# MiniRobot.net
KiCad netlist of a schematic drawn in EAGLE
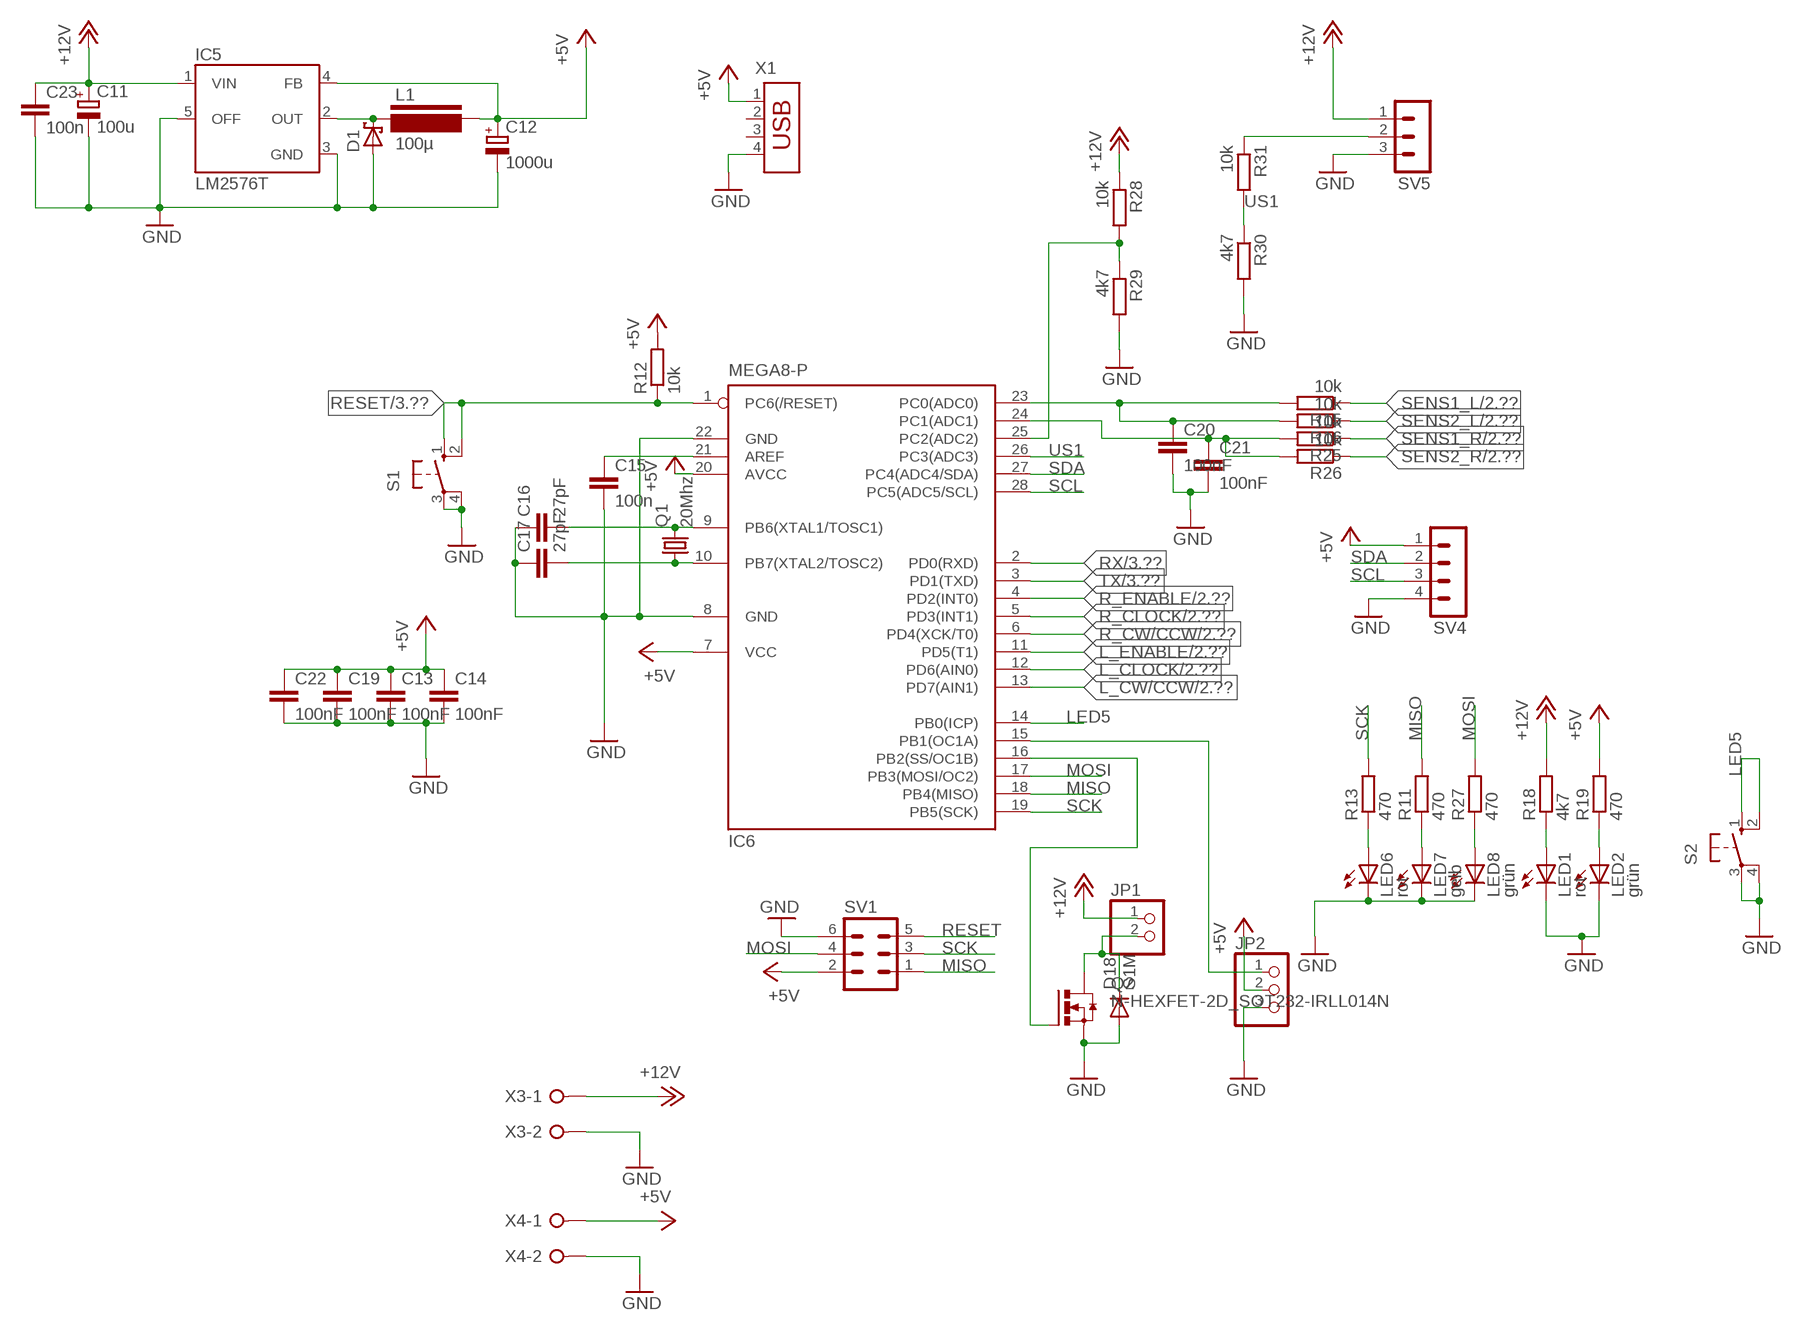
[diagram p0: schematic, sheet 1]
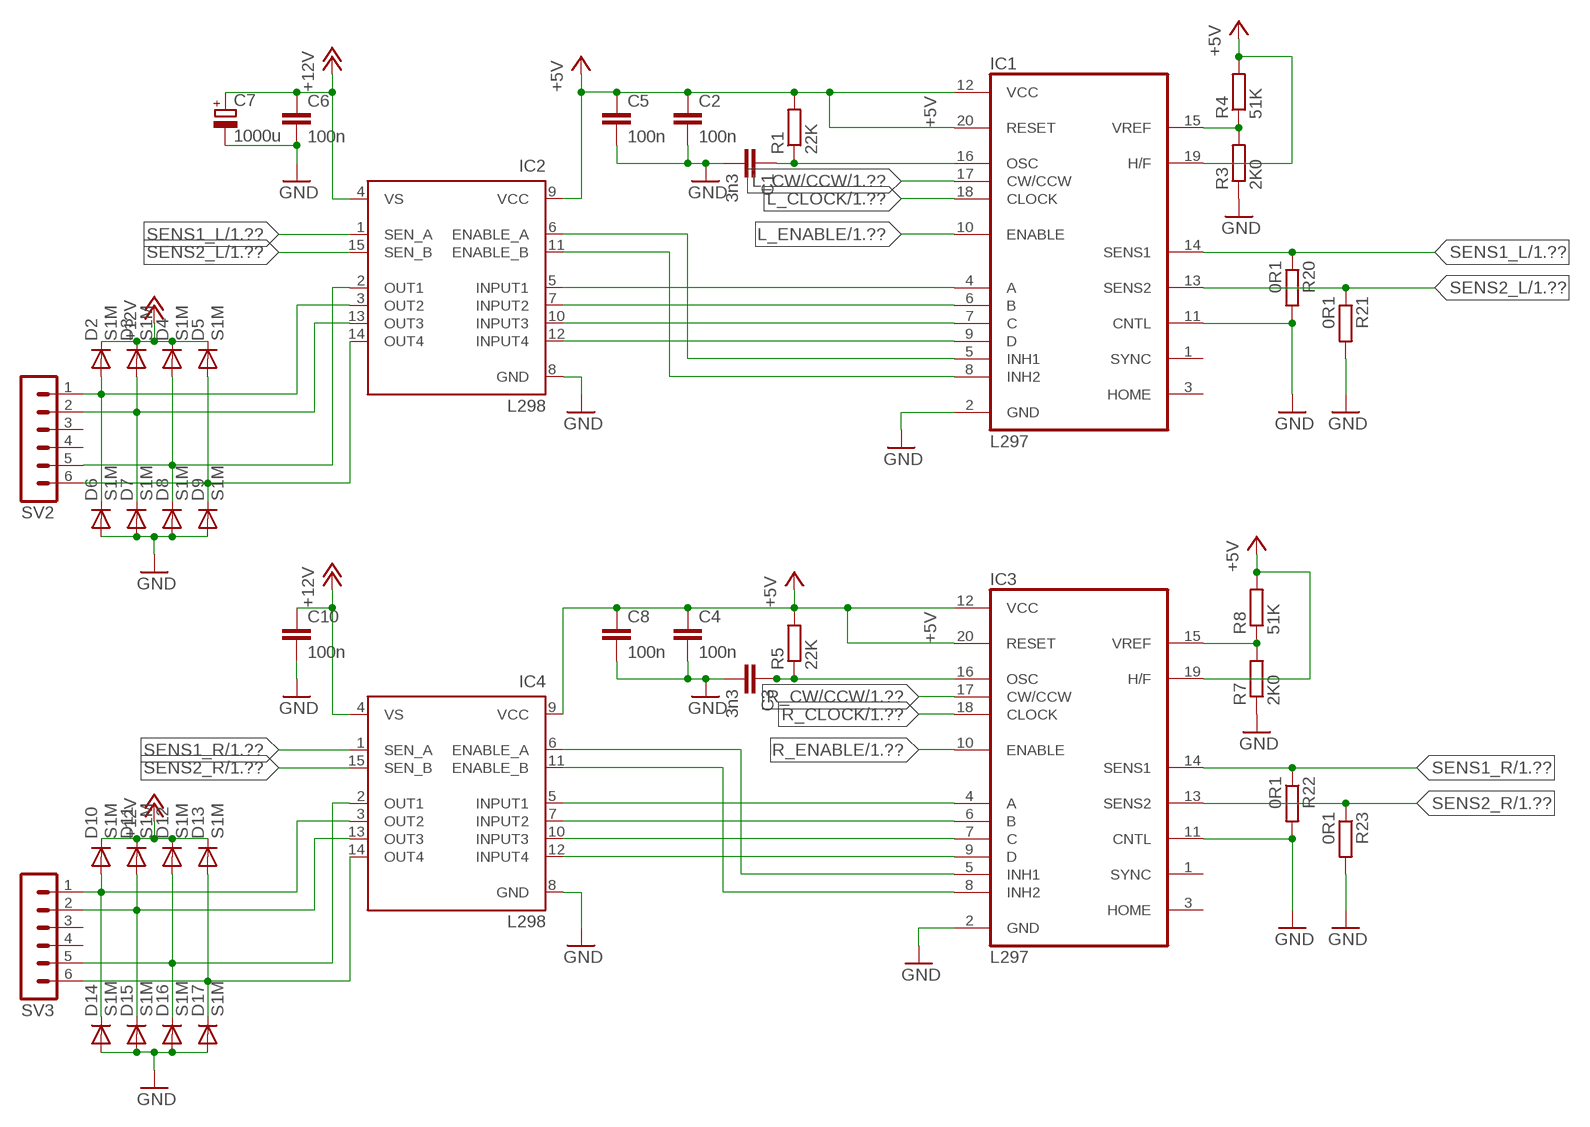
[diagram p1: schematic, sheet 2]
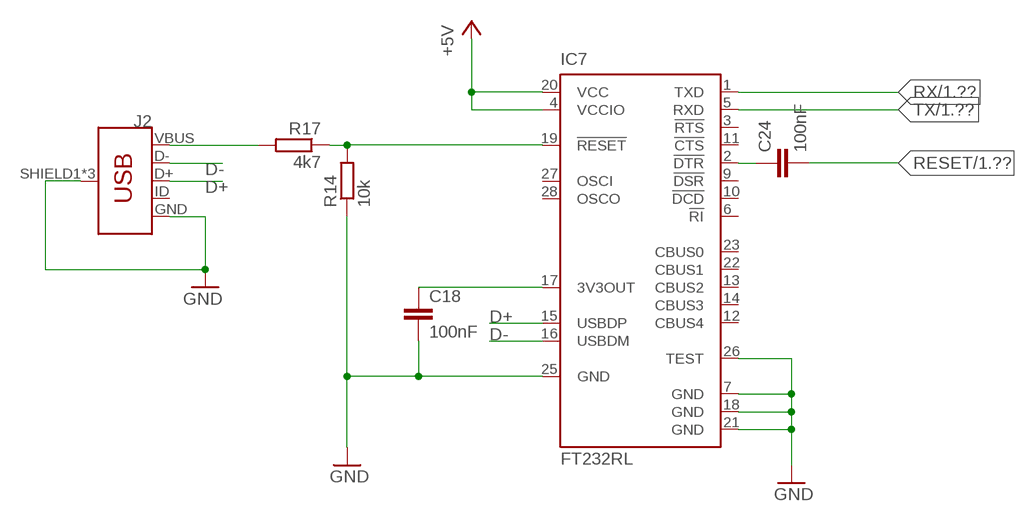
[diagram p2: schematic, sheet 3]

(export (version "E")
  (design (tool "Eeschema 10.0.6"))
  (components
    (comp (ref "C11")
      (value "100u")
      (footprint "eagle-import:E5-10,5")
      (libsource (lib "eagle-import") (part "CPOL-EUE5-10.5"))
    )
    (comp (ref "C12")
      (value "1000u")
      (footprint "eagle-import:E5-10,5")
      (libsource (lib "eagle-import") (part "CPOL-EUE5-10.5"))
    )
    (comp (ref "C13")
      (value "100nF")
      (footprint "eagle-import:C0805")
      (libsource (lib "eagle-import") (part "C-EUC0805"))
    )
    (comp (ref "C14")
      (value "100nF")
      (footprint "eagle-import:C0805")
      (libsource (lib "eagle-import") (part "C-EUC0805"))
    )
    (comp (ref "C15")
      (value "100n")
      (footprint "eagle-import:C0805")
      (libsource (lib "eagle-import") (part "C-EUC0805"))
    )
    (comp (ref "C16")
      (value "27pF")
      (footprint "eagle-import:C0805")
      (libsource (lib "eagle-import") (part "C-EUC0805"))
    )
    (comp (ref "C17")
      (value "27pF")
      (footprint "eagle-import:C0805")
      (libsource (lib "eagle-import") (part "C-EUC0805"))
    )
    (comp (ref "C19")
      (value "100nF")
      (footprint "eagle-import:C0805")
      (libsource (lib "eagle-import") (part "C-EUC0805"))
    )
    (comp (ref "C20")
      (value "100nF")
      (footprint "eagle-import:C0805")
      (libsource (lib "eagle-import") (part "C-EUC0805"))
    )
    (comp (ref "C21")
      (value "100nF")
      (footprint "eagle-import:C0805")
      (libsource (lib "eagle-import") (part "C-EUC0805"))
    )
    (comp (ref "C22")
      (value "100nF")
      (footprint "eagle-import:C0805")
      (libsource (lib "eagle-import") (part "C-EUC0805"))
    )
    (comp (ref "C23")
      (value "100n")
      (footprint "eagle-import:C0805")
      (libsource (lib "eagle-import") (part "resistor_C-EUC0805"))
    )
    (comp (ref "D1")
      (value "SCHOTTKY-DIODEF126Z12")
      (footprint "eagle-import:F126Z12")
      (libsource (lib "eagle-import") (part "SCHOTTKY-DIODEF126Z12"))
    )
    (comp (ref "D18")
      (value "S1M")
      (footprint "eagle-import:SMA")
      (libsource (lib "eagle-import") (part "S1M"))
    )
    (comp (ref "IC5")
      (value "LM2576T")
      (footprint "eagle-import:TO220-5")
      (libsource (lib "eagle-import") (part "LM2576T"))
    )
    (comp (ref "IC6")
      (value "MEGA8-P")
      (footprint "eagle-import:DIL28-3")
      (libsource (lib "eagle-import") (part "MEGA8-P"))
    )
    (comp (ref "JP1")
      (value "PINHD-1X2")
      (footprint "eagle-import:1X02")
      (libsource (lib "eagle-import") (part "PINHD-1X2"))
    )
    (comp (ref "JP2")
      (value "PINHD-1X3")
      (footprint "eagle-import:1X03")
      (libsource (lib "eagle-import") (part "PINHD-1X3"))
    )
    (comp (ref "L1")
      (value "100µ")
      (footprint "eagle-import:PISR")
      (libsource (lib "eagle-import") (part "L-PISR"))
    )
    (comp (ref "LED1")
      (value "rot")
      (footprint "eagle-import:CHIP-LED0805")
      (libsource (lib "eagle-import") (part "LEDCHIP-LED0805"))
    )
    (comp (ref "LED2")
      (value "grün")
      (footprint "eagle-import:CHIP-LED0805")
      (libsource (lib "eagle-import") (part "LEDCHIP-LED0805"))
    )
    (comp (ref "LED6")
      (value "rot")
      (footprint "eagle-import:CHIP-LED0805")
      (libsource (lib "eagle-import") (part "LEDCHIP-LED0805"))
    )
    (comp (ref "LED7")
      (value "gelb")
      (footprint "eagle-import:CHIP-LED0805")
      (libsource (lib "eagle-import") (part "LEDCHIP-LED0805"))
    )
    (comp (ref "LED8")
      (value "grün")
      (footprint "eagle-import:CHIP-LED0805")
      (libsource (lib "eagle-import") (part "LEDCHIP-LED0805"))
    )
    (comp (ref "Q1")
      (value "20Mhz")
      (footprint "eagle-import:CSM-7X-DU")
      (libsource (lib "eagle-import") (part "CSM-7X-DU"))
    )
    (comp (ref "Q2")
      (value "N-HEXFET-2D_SOT232-IRLL014N")
      (footprint "eagle-import:SOT223")
      (libsource (lib "eagle-import") (part "N-HEXFET-2D_?-SOT232IRLL014N"))
    )
    (comp (ref "R11")
      (value "470")
      (footprint "eagle-import:M0805")
      (libsource (lib "eagle-import") (part "R-EU_M0805"))
    )
    (comp (ref "R12")
      (value "10k")
      (footprint "eagle-import:R0805")
      (libsource (lib "eagle-import") (part "R-EU_R0805"))
    )
    (comp (ref "R13")
      (value "470")
      (footprint "eagle-import:M0805")
      (libsource (lib "eagle-import") (part "R-EU_M0805"))
    )
    (comp (ref "R15")
      (value "10k")
      (footprint "eagle-import:R0805")
      (libsource (lib "eagle-import") (part "R-EU_R0805"))
    )
    (comp (ref "R16")
      (value "10k")
      (footprint "eagle-import:M0805")
      (libsource (lib "eagle-import") (part "R-EU_M0805"))
    )
    (comp (ref "R18")
      (value "4k7")
      (footprint "eagle-import:R0805")
      (libsource (lib "eagle-import") (part "R-EU_R0805"))
    )
    (comp (ref "R19")
      (value "470")
      (footprint "eagle-import:M0805")
      (libsource (lib "eagle-import") (part "R-EU_M0805"))
    )
    (comp (ref "R25")
      (value "10k")
      (footprint "eagle-import:M0805")
      (libsource (lib "eagle-import") (part "R-EU_M0805"))
    )
    (comp (ref "R26")
      (value "10k")
      (footprint "eagle-import:M0805")
      (libsource (lib "eagle-import") (part "R-EU_M0805"))
    )
    (comp (ref "R27")
      (value "470")
      (footprint "eagle-import:R0805")
      (libsource (lib "eagle-import") (part "R-EU_R0805"))
    )
    (comp (ref "R28")
      (value "10k")
      (footprint "eagle-import:M0805")
      (libsource (lib "eagle-import") (part "R-EU_M0805"))
    )
    (comp (ref "R29")
      (value "4k7")
      (footprint "eagle-import:M0805")
      (libsource (lib "eagle-import") (part "R-EU_M0805"))
    )
    (comp (ref "R30")
      (value "4k7")
      (footprint "eagle-import:R0805")
      (libsource (lib "eagle-import") (part "R-EU_R0805"))
    )
    (comp (ref "R31")
      (value "10k")
      (footprint "eagle-import:R0805")
      (libsource (lib "eagle-import") (part "R-EU_R0805"))
    )
    (comp (ref "S1")
      (value "10-XX")
      (footprint "eagle-import:B3F-10XX")
      (fields (field (name "MPN") "B3F-1000"))
      (libsource (lib "eagle-import") (part "10-XX"))
    )
    (comp (ref "S2")
      (value "10-XX")
      (footprint "eagle-import:B3F-10XX")
      (fields (field (name "MPN") "B3F-1000"))
      (libsource (lib "eagle-import") (part "10-XX"))
    )
    (comp (ref "SV1")
      (value "ML6")
      (footprint "eagle-import:ML6")
      (libsource (lib "eagle-import") (part "ML6"))
    )
    (comp (ref "SV4")
      (value "MA04-1")
      (footprint "eagle-import:MA04-1")
      (libsource (lib "eagle-import") (part "MA04-1"))
    )
    (comp (ref "SV5")
      (value "MA03-1")
      (footprint "eagle-import:MA03-1")
      (libsource (lib "eagle-import") (part "MA03-1"))
    )
    (comp (ref "X1")
      (value "USB-787616")
      (footprint "eagle-import:USB")
      (libsource (lib "eagle-import") (part "USB-787616"))
    )
    (comp (ref "X3")
      (value "W237-02P")
      (footprint "eagle-import:W237-132")
      (libsource (lib "eagle-import") (part "W237-02P"))
    )
    (comp (ref "X4")
      (value "W237-02P")
      (footprint "eagle-import:W237-132")
      (libsource (lib "eagle-import") (part "W237-02P"))
    )
    (comp (ref "C1")
      (value "3n3")
      (footprint "eagle-import:C0805")
      (libsource (lib "eagle-import") (part "resistor_C-EUC0805"))
    )
    (comp (ref "C2")
      (value "100n")
      (footprint "eagle-import:C0805")
      (libsource (lib "eagle-import") (part "resistor_C-EUC0805"))
    )
    (comp (ref "C3")
      (value "3n3")
      (footprint "eagle-import:C0805")
      (libsource (lib "eagle-import") (part "resistor_C-EUC0805"))
    )
    (comp (ref "C4")
      (value "100n")
      (footprint "eagle-import:C0805")
      (libsource (lib "eagle-import") (part "resistor_C-EUC0805"))
    )
    (comp (ref "C5")
      (value "100n")
      (footprint "eagle-import:C0805")
      (libsource (lib "eagle-import") (part "resistor_C-EUC0805"))
    )
    (comp (ref "C6")
      (value "100n")
      (footprint "eagle-import:C0805")
      (libsource (lib "eagle-import") (part "resistor_C-EUC0805"))
    )
    (comp (ref "C7")
      (value "1000u")
      (footprint "eagle-import:E5-10,5")
      (libsource (lib "eagle-import") (part "CPOL-EUE5-10.5"))
    )
    (comp (ref "C8")
      (value "100n")
      (footprint "eagle-import:C0805")
      (libsource (lib "eagle-import") (part "resistor_C-EUC0805"))
    )
    (comp (ref "C10")
      (value "100n")
      (footprint "eagle-import:C0805")
      (libsource (lib "eagle-import") (part "resistor_C-EUC0805"))
    )
    (comp (ref "D2")
      (value "S1M")
      (footprint "eagle-import:SMA")
      (libsource (lib "eagle-import") (part "S1M"))
    )
    (comp (ref "D3")
      (value "S1M")
      (footprint "eagle-import:SMA")
      (libsource (lib "eagle-import") (part "S1M"))
    )
    (comp (ref "D4")
      (value "S1M")
      (footprint "eagle-import:SMA")
      (libsource (lib "eagle-import") (part "S1M"))
    )
    (comp (ref "D5")
      (value "S1M")
      (footprint "eagle-import:SMA")
      (libsource (lib "eagle-import") (part "S1M"))
    )
    (comp (ref "D6")
      (value "S1M")
      (footprint "eagle-import:SMA")
      (libsource (lib "eagle-import") (part "S1M"))
    )
    (comp (ref "D7")
      (value "S1M")
      (footprint "eagle-import:SMA")
      (libsource (lib "eagle-import") (part "S1M"))
    )
    (comp (ref "D8")
      (value "S1M")
      (footprint "eagle-import:SMA")
      (libsource (lib "eagle-import") (part "S1M"))
    )
    (comp (ref "D9")
      (value "S1M")
      (footprint "eagle-import:SMA")
      (libsource (lib "eagle-import") (part "S1M"))
    )
    (comp (ref "D10")
      (value "S1M")
      (footprint "eagle-import:SMA")
      (libsource (lib "eagle-import") (part "S1M"))
    )
    (comp (ref "D11")
      (value "S1M")
      (footprint "eagle-import:SMA")
      (libsource (lib "eagle-import") (part "S1M"))
    )
    (comp (ref "D12")
      (value "S1M")
      (footprint "eagle-import:SMA")
      (libsource (lib "eagle-import") (part "S1M"))
    )
    (comp (ref "D13")
      (value "S1M")
      (footprint "eagle-import:SMA")
      (libsource (lib "eagle-import") (part "S1M"))
    )
    (comp (ref "D14")
      (value "S1M")
      (footprint "eagle-import:SMA")
      (libsource (lib "eagle-import") (part "S1M"))
    )
    (comp (ref "D15")
      (value "S1M")
      (footprint "eagle-import:SMA")
      (libsource (lib "eagle-import") (part "S1M"))
    )
    (comp (ref "D16")
      (value "S1M")
      (footprint "eagle-import:SMA")
      (libsource (lib "eagle-import") (part "S1M"))
    )
    (comp (ref "D17")
      (value "S1M")
      (footprint "eagle-import:SMA")
      (libsource (lib "eagle-import") (part "S1M"))
    )
    (comp (ref "IC1")
      (value "L297")
      (footprint "eagle-import:DIL20")
      (fields (field (name "MPN") "L297/1"))
      (libsource (lib "eagle-import") (part "L297"))
    )
    (comp (ref "IC2")
      (value "L298")
      (footprint "eagle-import:MULTIWATT-15")
      (fields (field (name "MPN") "L298N"))
      (libsource (lib "eagle-import") (part "L298"))
    )
    (comp (ref "IC3")
      (value "L297")
      (footprint "eagle-import:DIL20")
      (fields (field (name "MPN") "L297/1"))
      (libsource (lib "eagle-import") (part "L297"))
    )
    (comp (ref "IC4")
      (value "L298")
      (footprint "eagle-import:MULTIWATT-15")
      (fields (field (name "MPN") "L298N"))
      (libsource (lib "eagle-import") (part "L298"))
    )
    (comp (ref "R1")
      (value "22K")
      (footprint "eagle-import:R0805")
      (libsource (lib "eagle-import") (part "R-EU_R0805"))
    )
    (comp (ref "R3")
      (value "2K0")
      (footprint "eagle-import:R0805")
      (libsource (lib "eagle-import") (part "R-EU_R0805"))
    )
    (comp (ref "R4")
      (value "51K")
      (footprint "eagle-import:R0805")
      (libsource (lib "eagle-import") (part "R-EU_R0805"))
    )
    (comp (ref "R5")
      (value "22K")
      (footprint "eagle-import:R0805")
      (libsource (lib "eagle-import") (part "R-EU_R0805"))
    )
    (comp (ref "R7")
      (value "2K0")
      (footprint "eagle-import:R0805")
      (libsource (lib "eagle-import") (part "R-EU_R0805"))
    )
    (comp (ref "R8")
      (value "51K")
      (footprint "eagle-import:R0805")
      (libsource (lib "eagle-import") (part "R-EU_R0805"))
    )
    (comp (ref "R20")
      (value "0R1")
      (footprint "eagle-import:P0613_15")
      (libsource (lib "eagle-import") (part "R-EU_0613/15"))
    )
    (comp (ref "R21")
      (value "0R1")
      (footprint "eagle-import:P0613_15")
      (libsource (lib "eagle-import") (part "R-EU_0613/15"))
    )
    (comp (ref "R22")
      (value "0R1")
      (footprint "eagle-import:P0613_15")
      (libsource (lib "eagle-import") (part "R-EU_0613/15"))
    )
    (comp (ref "R23")
      (value "0R1")
      (footprint "eagle-import:P0613_15")
      (libsource (lib "eagle-import") (part "R-EU_0613/15"))
    )
    (comp (ref "SV2")
      (value "MA06-1")
      (footprint "eagle-import:MA06-1")
      (libsource (lib "eagle-import") (part "MA06-1"))
    )
    (comp (ref "SV3")
      (value "MA06-1")
      (footprint "eagle-import:MA06-1")
      (libsource (lib "eagle-import") (part "MA06-1"))
    )
    (comp (ref "C18")
      (value "100nF")
      (footprint "eagle-import:C0805")
      (libsource (lib "eagle-import") (part "C-EUC0805"))
    )
    (comp (ref "C24")
      (value "100nF")
      (footprint "eagle-import:C0805")
      (libsource (lib "eagle-import") (part "C-EUC0805"))
    )
    (comp (ref "IC7")
      (value "FT232RL")
      (footprint "eagle-import:SSOP28")
      (libsource (lib "eagle-import") (part "FT232RL"))
    )
    (comp (ref "J2")
      (value "USB_MICRO-B_FEMALE-SMT")
      (footprint "eagle-import:USB-B-MICRO-SMD")
      (libsource (lib "eagle-import") (part "USB_MICRO-B_FEMALE-SMT"))
    )
    (comp (ref "R14")
      (value "10k")
      (footprint "eagle-import:M0805")
      (libsource (lib "eagle-import") (part "R-EU_M0805"))
    )
    (comp (ref "R17")
      (value "4k7")
      (footprint "eagle-import:M0805")
      (libsource (lib "eagle-import") (part "R-EU_M0805"))
    )
  )
  (nets
    (net (code "1") (name "+5V") (class "Default")
      (node (ref "C12") (pin "+") (pinfunction "+_+") (pintype "passive"))
      (node (ref "C13") (pin "1") (pinfunction "1_1") (pintype "passive"))
      (node (ref "C14") (pin "1") (pinfunction "1_1") (pintype "passive"))
      (node (ref "C19") (pin "1") (pinfunction "1_1") (pintype "passive"))
      (node (ref "C2") (pin "1") (pinfunction "1_1") (pintype "passive"))
      (node (ref "C22") (pin "1") (pinfunction "1_1") (pintype "passive"))
      (node (ref "C4") (pin "1") (pinfunction "1_1") (pintype "passive"))
      (node (ref "C5") (pin "1") (pinfunction "1_1") (pintype "passive"))
      (node (ref "C8") (pin "1") (pinfunction "1_1") (pintype "passive"))
      (node (ref "IC1") (pin "12") (pinfunction "VCC_12") (pintype "power_in"))
      (node (ref "IC1") (pin "19") (pinfunction "H/F_19") (pintype "input"))
      (node (ref "IC1") (pin "20") (pinfunction "RESET_20") (pintype "input"))
      (node (ref "IC2") (pin "9") (pinfunction "VCC_9") (pintype "power_in"))
      (node (ref "IC3") (pin "12") (pinfunction "VCC_12") (pintype "power_in"))
      (node (ref "IC3") (pin "19") (pinfunction "H/F_19") (pintype "input"))
      (node (ref "IC3") (pin "20") (pinfunction "RESET_20") (pintype "input"))
      (node (ref "IC4") (pin "9") (pinfunction "VCC_9") (pintype "power_in"))
      (node (ref "IC5") (pin "4") (pinfunction "FB_4") (pintype "input"))
      (node (ref "IC6") (pin "20") (pinfunction "AVCC_20") (pintype "power_in"))
      (node (ref "IC6") (pin "7") (pinfunction "VCC_7") (pintype "power_in"))
      (node (ref "IC7") (pin "20") (pinfunction "VCC_20") (pintype "power_in"))
      (node (ref "IC7") (pin "4") (pinfunction "VCCIO_4") (pintype "power_in"))
      (node (ref "JP2") (pin "2") (pinfunction "2_2") (pintype "passive"))
      (node (ref "L1") (pin "P$2") (pinfunction "P$2_P$2") (pintype "passive"))
      (node (ref "R1") (pin "2") (pinfunction "2_2") (pintype "passive"))
      (node (ref "R12") (pin "2") (pinfunction "2_2") (pintype "passive"))
      (node (ref "R19") (pin "2") (pinfunction "2_2") (pintype "passive"))
      (node (ref "R4") (pin "2") (pinfunction "2_2") (pintype "passive"))
      (node (ref "R5") (pin "2") (pinfunction "2_2") (pintype "passive"))
      (node (ref "R8") (pin "2") (pinfunction "2_2") (pintype "passive"))
      (node (ref "SV1") (pin "2") (pinfunction "2_2") (pintype "passive"))
      (node (ref "SV4") (pin "1") (pinfunction "1_1") (pintype "passive"))
      (node (ref "X1") (pin "1") (pinfunction "1_1") (pintype "passive"))
      (node (ref "X4") (pin "1") (pinfunction "KL_1") (pintype "passive"))
    )
    (net (code "2") (name "+12V") (class "Default")
      (node (ref "C10") (pin "1") (pinfunction "1_1") (pintype "passive"))
      (node (ref "C11") (pin "+") (pinfunction "+_+") (pintype "passive"))
      (node (ref "C23") (pin "1") (pinfunction "1_1") (pintype "passive"))
      (node (ref "C6") (pin "1") (pinfunction "1_1") (pintype "passive"))
      (node (ref "C7") (pin "+") (pinfunction "+_+") (pintype "passive"))
      (node (ref "D10") (pin "C") (pinfunction "C_C") (pintype "passive"))
      (node (ref "D11") (pin "C") (pinfunction "C_C") (pintype "passive"))
      (node (ref "D12") (pin "C") (pinfunction "C_C") (pintype "passive"))
      (node (ref "D13") (pin "C") (pinfunction "C_C") (pintype "passive"))
      (node (ref "D2") (pin "C") (pinfunction "C_C") (pintype "passive"))
      (node (ref "D3") (pin "C") (pinfunction "C_C") (pintype "passive"))
      (node (ref "D4") (pin "C") (pinfunction "C_C") (pintype "passive"))
      (node (ref "D5") (pin "C") (pinfunction "C_C") (pintype "passive"))
      (node (ref "IC2") (pin "4") (pinfunction "VS_4") (pintype "power_in"))
      (node (ref "IC4") (pin "4") (pinfunction "VS_4") (pintype "power_in"))
      (node (ref "IC5") (pin "1") (pinfunction "VIN_1") (pintype "power_in"))
      (node (ref "JP1") (pin "1") (pinfunction "1_1") (pintype "passive"))
      (node (ref "R18") (pin "2") (pinfunction "2_2") (pintype "passive"))
      (node (ref "R28") (pin "1") (pinfunction "1_1") (pintype "passive"))
      (node (ref "SV5") (pin "1") (pinfunction "1_1") (pintype "passive"))
      (node (ref "X3") (pin "1") (pinfunction "KL_1") (pintype "passive"))
    )
    (net (code "3") (name "D+") (class "Default")
      (node (ref "IC7") (pin "15") (pinfunction "USBDP_15") (pintype "bidirectional"))
      (node (ref "J2") (pin "D+") (pinfunction "D+_D+") (pintype "bidirectional"))
    )
    (net (code "4") (name "D-") (class "Default")
      (node (ref "IC7") (pin "16") (pinfunction "USBDM_16") (pintype "bidirectional"))
      (node (ref "J2") (pin "D-") (pinfunction "D-_D-") (pintype "bidirectional"))
    )
    (net (code "5") (name "GND") (class "Default")
      (node (ref "C1") (pin "2") (pinfunction "2_2") (pintype "passive"))
      (node (ref "C10") (pin "2") (pinfunction "2_2") (pintype "passive"))
      (node (ref "C11") (pin "-") (pinfunction "-_-") (pintype "passive"))
      (node (ref "C12") (pin "-") (pinfunction "-_-") (pintype "passive"))
      (node (ref "C13") (pin "2") (pinfunction "2_2") (pintype "passive"))
      (node (ref "C14") (pin "2") (pinfunction "2_2") (pintype "passive"))
      (node (ref "C15") (pin "2") (pinfunction "2_2") (pintype "passive"))
      (node (ref "C16") (pin "1") (pinfunction "1_1") (pintype "passive"))
      (node (ref "C17") (pin "1") (pinfunction "1_1") (pintype "passive"))
      (node (ref "C18") (pin "2") (pinfunction "2_2") (pintype "passive"))
      (node (ref "C19") (pin "2") (pinfunction "2_2") (pintype "passive"))
      (node (ref "C2") (pin "2") (pinfunction "2_2") (pintype "passive"))
      (node (ref "C20") (pin "2") (pinfunction "2_2") (pintype "passive"))
      (node (ref "C21") (pin "2") (pinfunction "2_2") (pintype "passive"))
      (node (ref "C22") (pin "2") (pinfunction "2_2") (pintype "passive"))
      (node (ref "C23") (pin "2") (pinfunction "2_2") (pintype "passive"))
      (node (ref "C3") (pin "2") (pinfunction "2_2") (pintype "passive"))
      (node (ref "C4") (pin "2") (pinfunction "2_2") (pintype "passive"))
      (node (ref "C5") (pin "2") (pinfunction "2_2") (pintype "passive"))
      (node (ref "C6") (pin "2") (pinfunction "2_2") (pintype "passive"))
      (node (ref "C7") (pin "-") (pinfunction "-_-") (pintype "passive"))
      (node (ref "C8") (pin "2") (pinfunction "2_2") (pintype "passive"))
      (node (ref "D1") (pin "A") (pinfunction "A_A") (pintype "passive"))
      (node (ref "D14") (pin "A") (pinfunction "A_A") (pintype "passive"))
      (node (ref "D15") (pin "A") (pinfunction "A_A") (pintype "passive"))
      (node (ref "D16") (pin "A") (pinfunction "A_A") (pintype "passive"))
      (node (ref "D17") (pin "A") (pinfunction "A_A") (pintype "passive"))
      (node (ref "D18") (pin "A") (pinfunction "A_A") (pintype "passive"))
      (node (ref "D6") (pin "A") (pinfunction "A_A") (pintype "passive"))
      (node (ref "D7") (pin "A") (pinfunction "A_A") (pintype "passive"))
      (node (ref "D8") (pin "A") (pinfunction "A_A") (pintype "passive"))
      (node (ref "D9") (pin "A") (pinfunction "A_A") (pintype "passive"))
      (node (ref "IC1") (pin "11") (pinfunction "CNTL_11") (pintype "input"))
      (node (ref "IC1") (pin "2") (pinfunction "GND_2") (pintype "power_in"))
      (node (ref "IC2") (pin "8") (pinfunction "GND_8") (pintype "power_in"))
      (node (ref "IC3") (pin "11") (pinfunction "CNTL_11") (pintype "input"))
      (node (ref "IC3") (pin "2") (pinfunction "GND_2") (pintype "power_in"))
      (node (ref "IC4") (pin "8") (pinfunction "GND_8") (pintype "power_in"))
      (node (ref "IC5") (pin "3") (pinfunction "GND_3") (pintype "power_in"))
      (node (ref "IC5") (pin "5") (pinfunction "OFF_5") (pintype "input"))
      (node (ref "IC6") (pin "22") (pinfunction "GND_22") (pintype "power_in"))
      (node (ref "IC6") (pin "8") (pinfunction "GND_8") (pintype "power_in"))
      (node (ref "IC7") (pin "18") (pinfunction "GND_18") (pintype "power_in"))
      (node (ref "IC7") (pin "21") (pinfunction "GND_21") (pintype "power_in"))
      (node (ref "IC7") (pin "25") (pinfunction "GND_25") (pintype "power_in"))
      (node (ref "IC7") (pin "26") (pinfunction "TEST_26") (pintype "input"))
      (node (ref "IC7") (pin "7") (pinfunction "GND_7") (pintype "power_in"))
      (node (ref "J2") (pin "GND") (pinfunction "GND_GND") (pintype "power_in"))
      (node (ref "J2") (pin "SHIELD1") (pinfunction "SHIELD_SHIELD1") (pintype "bidirectional"))
      (node (ref "J2") (pin "SHIELD2") (pinfunction "SHIELD_SHIELD2") (pintype "bidirectional"))
      (node (ref "J2") (pin "SHIELD3") (pinfunction "SHIELD_SHIELD3") (pintype "bidirectional"))
      (node (ref "JP2") (pin "3") (pinfunction "3_3") (pintype "passive"))
      (node (ref "LED1") (pin "C") (pinfunction "C_C") (pintype "passive"))
      (node (ref "LED2") (pin "C") (pinfunction "C_C") (pintype "passive"))
      (node (ref "LED6") (pin "C") (pinfunction "C_C") (pintype "passive"))
      (node (ref "LED7") (pin "C") (pinfunction "C_C") (pintype "passive"))
      (node (ref "LED8") (pin "C") (pinfunction "C_C") (pintype "passive"))
      (node (ref "Q2") (pin "3") (pinfunction "S_3") (pintype "passive"))
      (node (ref "R14") (pin "1") (pinfunction "1_1") (pintype "passive"))
      (node (ref "R20") (pin "2") (pinfunction "2_2") (pintype "passive"))
      (node (ref "R21") (pin "2") (pinfunction "2_2") (pintype "passive"))
      (node (ref "R22") (pin "2") (pinfunction "2_2") (pintype "passive"))
      (node (ref "R23") (pin "2") (pinfunction "2_2") (pintype "passive"))
      (node (ref "R29") (pin "2") (pinfunction "2_2") (pintype "passive"))
      (node (ref "R3") (pin "1") (pinfunction "1_1") (pintype "passive"))
      (node (ref "R30") (pin "2") (pinfunction "2_2") (pintype "passive"))
      (node (ref "R7") (pin "1") (pinfunction "1_1") (pintype "passive"))
      (node (ref "S1") (pin "3") (pinfunction "P_3") (pintype "passive"))
      (node (ref "S1") (pin "4") (pinfunction "P1_4") (pintype "passive"))
      (node (ref "S2") (pin "3") (pinfunction "P_3") (pintype "passive"))
      (node (ref "S2") (pin "4") (pinfunction "P1_4") (pintype "passive"))
      (node (ref "SV1") (pin "6") (pinfunction "6_6") (pintype "passive"))
      (node (ref "SV4") (pin "4") (pinfunction "4_4") (pintype "passive"))
      (node (ref "SV5") (pin "3") (pinfunction "3_3") (pintype "passive"))
      (node (ref "X1") (pin "4") (pinfunction "4_4") (pintype "passive"))
      (node (ref "X3") (pin "2") (pinfunction "KL_2") (pintype "passive"))
      (node (ref "X4") (pin "2") (pinfunction "KL_2") (pintype "passive"))
    )
    (net (code "6") (name "LED5") (class "Default")
      (node (ref "IC6") (pin "14") (pinfunction "PB0(ICP)_14") (pintype "bidirectional"))
      (node (ref "S2") (pin "1") (pinfunction "S_1") (pintype "passive"))
      (node (ref "S2") (pin "2") (pinfunction "S1_2") (pintype "passive"))
    )
    (net (code "7") (name "L_CLOCK") (class "Default")
      (node (ref "IC1") (pin "18") (pinfunction "CLOCK_18") (pintype "input"))
      (node (ref "IC6") (pin "12") (pinfunction "PD6(AIN0)_12") (pintype "bidirectional"))
    )
    (net (code "8") (name "L_CW{slash}CCW") (class "Default")
      (node (ref "IC1") (pin "17") (pinfunction "CW/CCW_17") (pintype "input"))
      (node (ref "IC6") (pin "13") (pinfunction "PD7(AIN1)_13") (pintype "bidirectional"))
    )
    (net (code "9") (name "L_ENABLE") (class "Default")
      (node (ref "IC1") (pin "10") (pinfunction "ENABLE_10") (pintype "input"))
      (node (ref "IC6") (pin "11") (pinfunction "PD5(T1)_11") (pintype "bidirectional"))
    )
    (net (code "10") (name "MISO") (class "Default")
      (node (ref "IC6") (pin "18") (pinfunction "PB4(MISO)_18") (pintype "bidirectional"))
      (node (ref "R11") (pin "2") (pinfunction "2_2") (pintype "passive"))
      (node (ref "SV1") (pin "1") (pinfunction "1_1") (pintype "passive"))
    )
    (net (code "11") (name "MOSI") (class "Default")
      (node (ref "IC6") (pin "17") (pinfunction "PB3(MOSI/OC2)_17") (pintype "bidirectional"))
      (node (ref "R27") (pin "2") (pinfunction "2_2") (pintype "passive"))
      (node (ref "SV1") (pin "4") (pinfunction "4_4") (pintype "passive"))
    )
    (net (code "12") (name "Net-(D18-PadC)") (class "Default")
      (node (ref "D18") (pin "C") (pinfunction "C_C") (pintype "passive"))
      (node (ref "JP1") (pin "2") (pinfunction "2_2") (pintype "passive"))
      (node (ref "Q2") (pin "2") (pinfunction "D_2") (pintype "passive"))
      (node (ref "Q2") (pin "4") (pinfunction "D_4") (pintype "passive"))
    )
    (net (code "13") (name "Net-(IC1-A)") (class "Default")
      (node (ref "IC1") (pin "4") (pinfunction "A_4") (pintype "output"))
      (node (ref "IC2") (pin "5") (pinfunction "INPUT1_5") (pintype "input"))
    )
    (net (code "14") (name "Net-(IC1-B)") (class "Default")
      (node (ref "IC1") (pin "6") (pinfunction "B_6") (pintype "output"))
      (node (ref "IC2") (pin "7") (pinfunction "INPUT2_7") (pintype "input"))
    )
    (net (code "15") (name "Net-(IC1-C)") (class "Default")
      (node (ref "IC1") (pin "7") (pinfunction "C_7") (pintype "output"))
      (node (ref "IC2") (pin "10") (pinfunction "INPUT3_10") (pintype "input"))
    )
    (net (code "16") (name "Net-(IC1-D)") (class "Default")
      (node (ref "IC1") (pin "9") (pinfunction "D_9") (pintype "output"))
      (node (ref "IC2") (pin "12") (pinfunction "INPUT4_12") (pintype "input"))
    )
    (net (code "17") (name "Net-(IC1-INH1)") (class "Default")
      (node (ref "IC1") (pin "5") (pinfunction "INH1_5") (pintype "output"))
      (node (ref "IC2") (pin "6") (pinfunction "ENABLE_A_6") (pintype "input"))
    )
    (net (code "18") (name "Net-(IC1-INH2)") (class "Default")
      (node (ref "IC1") (pin "8") (pinfunction "INH2_8") (pintype "output"))
      (node (ref "IC2") (pin "11") (pinfunction "ENABLE_B_11") (pintype "input"))
    )
    (net (code "19") (name "Net-(IC1-OSC)") (class "Default")
      (node (ref "C1") (pin "1") (pinfunction "1_1") (pintype "passive"))
      (node (ref "IC1") (pin "16") (pinfunction "OSC_16") (pintype "bidirectional"))
      (node (ref "R1") (pin "1") (pinfunction "1_1") (pintype "passive"))
    )
    (net (code "20") (name "Net-(IC1-VREF)") (class "Default")
      (node (ref "IC1") (pin "15") (pinfunction "VREF_15") (pintype "input"))
      (node (ref "R3") (pin "2") (pinfunction "2_2") (pintype "passive"))
      (node (ref "R4") (pin "1") (pinfunction "1_1") (pintype "passive"))
    )
    (net (code "21") (name "Net-(IC2-OUT1)") (class "Default")
      (node (ref "D4") (pin "A") (pinfunction "A_A") (pintype "passive"))
      (node (ref "D8") (pin "C") (pinfunction "C_C") (pintype "passive"))
      (node (ref "IC2") (pin "2") (pinfunction "OUT1_2") (pintype "output"))
      (node (ref "SV2") (pin "5") (pinfunction "5_5") (pintype "passive"))
    )
    (net (code "22") (name "Net-(IC2-OUT2)") (class "Default")
      (node (ref "D2") (pin "A") (pinfunction "A_A") (pintype "passive"))
      (node (ref "D6") (pin "C") (pinfunction "C_C") (pintype "passive"))
      (node (ref "IC2") (pin "3") (pinfunction "OUT2_3") (pintype "output"))
      (node (ref "SV2") (pin "1") (pinfunction "1_1") (pintype "passive"))
    )
    (net (code "23") (name "Net-(IC2-OUT3)") (class "Default")
      (node (ref "D3") (pin "A") (pinfunction "A_A") (pintype "passive"))
      (node (ref "D7") (pin "C") (pinfunction "C_C") (pintype "passive"))
      (node (ref "IC2") (pin "13") (pinfunction "OUT3_13") (pintype "output"))
      (node (ref "SV2") (pin "2") (pinfunction "2_2") (pintype "passive"))
    )
    (net (code "24") (name "Net-(IC2-OUT4)") (class "Default")
      (node (ref "D5") (pin "A") (pinfunction "A_A") (pintype "passive"))
      (node (ref "D9") (pin "C") (pinfunction "C_C") (pintype "passive"))
      (node (ref "IC2") (pin "14") (pinfunction "OUT4_14") (pintype "output"))
      (node (ref "SV2") (pin "6") (pinfunction "6_6") (pintype "passive"))
    )
    (net (code "25") (name "Net-(IC3-A)") (class "Default")
      (node (ref "IC3") (pin "4") (pinfunction "A_4") (pintype "output"))
      (node (ref "IC4") (pin "5") (pinfunction "INPUT1_5") (pintype "input"))
    )
    (net (code "26") (name "Net-(IC3-B)") (class "Default")
      (node (ref "IC3") (pin "6") (pinfunction "B_6") (pintype "output"))
      (node (ref "IC4") (pin "7") (pinfunction "INPUT2_7") (pintype "input"))
    )
    (net (code "27") (name "Net-(IC3-C)") (class "Default")
      (node (ref "IC3") (pin "7") (pinfunction "C_7") (pintype "output"))
      (node (ref "IC4") (pin "10") (pinfunction "INPUT3_10") (pintype "input"))
    )
    (net (code "28") (name "Net-(IC3-D)") (class "Default")
      (node (ref "IC3") (pin "9") (pinfunction "D_9") (pintype "output"))
      (node (ref "IC4") (pin "12") (pinfunction "INPUT4_12") (pintype "input"))
    )
    (net (code "29") (name "Net-(IC3-INH1)") (class "Default")
      (node (ref "IC3") (pin "5") (pinfunction "INH1_5") (pintype "output"))
      (node (ref "IC4") (pin "6") (pinfunction "ENABLE_A_6") (pintype "input"))
    )
    (net (code "30") (name "Net-(IC3-INH2)") (class "Default")
      (node (ref "IC3") (pin "8") (pinfunction "INH2_8") (pintype "output"))
      (node (ref "IC4") (pin "11") (pinfunction "ENABLE_B_11") (pintype "input"))
    )
    (net (code "31") (name "Net-(IC3-OSC)") (class "Default")
      (node (ref "C3") (pin "1") (pinfunction "1_1") (pintype "passive"))
      (node (ref "IC3") (pin "16") (pinfunction "OSC_16") (pintype "bidirectional"))
      (node (ref "R5") (pin "1") (pinfunction "1_1") (pintype "passive"))
    )
    (net (code "32") (name "Net-(IC3-VREF)") (class "Default")
      (node (ref "IC3") (pin "15") (pinfunction "VREF_15") (pintype "input"))
      (node (ref "R7") (pin "2") (pinfunction "2_2") (pintype "passive"))
      (node (ref "R8") (pin "1") (pinfunction "1_1") (pintype "passive"))
    )
    (net (code "33") (name "Net-(IC4-OUT1)") (class "Default")
      (node (ref "D12") (pin "A") (pinfunction "A_A") (pintype "passive"))
      (node (ref "D16") (pin "C") (pinfunction "C_C") (pintype "passive"))
      (node (ref "IC4") (pin "2") (pinfunction "OUT1_2") (pintype "output"))
      (node (ref "SV3") (pin "5") (pinfunction "5_5") (pintype "passive"))
    )
    (net (code "34") (name "Net-(IC4-OUT2)") (class "Default")
      (node (ref "D10") (pin "A") (pinfunction "A_A") (pintype "passive"))
      (node (ref "D14") (pin "C") (pinfunction "C_C") (pintype "passive"))
      (node (ref "IC4") (pin "3") (pinfunction "OUT2_3") (pintype "output"))
      (node (ref "SV3") (pin "1") (pinfunction "1_1") (pintype "passive"))
    )
    (net (code "35") (name "Net-(IC4-OUT3)") (class "Default")
      (node (ref "D11") (pin "A") (pinfunction "A_A") (pintype "passive"))
      (node (ref "D15") (pin "C") (pinfunction "C_C") (pintype "passive"))
      (node (ref "IC4") (pin "13") (pinfunction "OUT3_13") (pintype "output"))
      (node (ref "SV3") (pin "2") (pinfunction "2_2") (pintype "passive"))
    )
    (net (code "36") (name "Net-(IC4-OUT4)") (class "Default")
      (node (ref "D13") (pin "A") (pinfunction "A_A") (pintype "passive"))
      (node (ref "D17") (pin "C") (pinfunction "C_C") (pintype "passive"))
      (node (ref "IC4") (pin "14") (pinfunction "OUT4_14") (pintype "output"))
      (node (ref "SV3") (pin "6") (pinfunction "6_6") (pintype "passive"))
    )
    (net (code "37") (name "Net-(IC5-OUT)") (class "Default")
      (node (ref "D1") (pin "C") (pinfunction "C_C") (pintype "passive"))
      (node (ref "IC5") (pin "2") (pinfunction "OUT_2") (pintype "output"))
      (node (ref "L1") (pin "P$1") (pinfunction "P$1_P$1") (pintype "passive"))
    )
    (net (code "38") (name "Net-(IC6-AREF)") (class "Default")
      (node (ref "C15") (pin "1") (pinfunction "1_1") (pintype "passive"))
      (node (ref "IC6") (pin "21") (pinfunction "AREF_21") (pintype "passive"))
    )
    (net (code "39") (name "Net-(IC6-PB1(OC1A))") (class "Default")
      (node (ref "IC6") (pin "15") (pinfunction "PB1(OC1A)_15") (pintype "bidirectional"))
      (node (ref "JP2") (pin "1") (pinfunction "1_1") (pintype "passive"))
    )
    (net (code "40") (name "Net-(IC6-PB2(SS{slash}OC1B))") (class "Default")
      (node (ref "IC6") (pin "16") (pinfunction "PB2(SS/OC1B)_16") (pintype "bidirectional"))
      (node (ref "Q2") (pin "1") (pinfunction "G_1") (pintype "passive"))
    )
    (net (code "41") (name "Net-(IC6-PB6(XTAL1{slash}TOSC1))") (class "Default")
      (node (ref "C16") (pin "2") (pinfunction "2_2") (pintype "passive"))
      (node (ref "IC6") (pin "9") (pinfunction "PB6(XTAL1/TOSC1)_9") (pintype "bidirectional"))
      (node (ref "Q1") (pin "2") (pinfunction "2_2") (pintype "passive"))
    )
    (net (code "42") (name "Net-(IC6-PB7(XTAL2{slash}TOSC2))") (class "Default")
      (node (ref "C17") (pin "2") (pinfunction "2_2") (pintype "passive"))
      (node (ref "IC6") (pin "10") (pinfunction "PB7(XTAL2/TOSC2)_10") (pintype "bidirectional"))
      (node (ref "Q1") (pin "1") (pinfunction "1_1") (pintype "passive"))
    )
    (net (code "43") (name "Net-(IC6-PC0(ADC0))") (class "Default")
      (node (ref "C20") (pin "1") (pinfunction "1_1") (pintype "passive"))
      (node (ref "IC6") (pin "23") (pinfunction "PC0(ADC0)_23") (pintype "bidirectional"))
      (node (ref "R15") (pin "2") (pinfunction "2_2") (pintype "passive"))
      (node (ref "R16") (pin "2") (pinfunction "2_2") (pintype "passive"))
    )
    (net (code "44") (name "Net-(IC6-PC1(ADC1))") (class "Default")
      (node (ref "C21") (pin "1") (pinfunction "1_1") (pintype "passive"))
      (node (ref "IC6") (pin "24") (pinfunction "PC1(ADC1)_24") (pintype "bidirectional"))
      (node (ref "R25") (pin "2") (pinfunction "2_2") (pintype "passive"))
      (node (ref "R26") (pin "2") (pinfunction "2_2") (pintype "passive"))
    )
    (net (code "45") (name "Net-(IC6-PC2(ADC2))") (class "Default")
      (node (ref "IC6") (pin "25") (pinfunction "PC2(ADC2)_25") (pintype "bidirectional"))
      (node (ref "R28") (pin "2") (pinfunction "2_2") (pintype "passive"))
      (node (ref "R29") (pin "1") (pinfunction "1_1") (pintype "passive"))
    )
    (net (code "46") (name "Net-(IC7-3V3OUT)") (class "Default")
      (node (ref "C18") (pin "1") (pinfunction "1_1") (pintype "passive"))
      (node (ref "IC7") (pin "17") (pinfunction "3V3OUT_17") (pintype "output"))
    )
    (net (code "47") (name "Net-(IC7-~{DTR})") (class "Default")
      (node (ref "C24") (pin "1") (pinfunction "1_1") (pintype "passive"))
      (node (ref "IC7") (pin "2") (pinfunction "~{DTR}_2") (pintype "output"))
    )
    (net (code "48") (name "Net-(IC7-~{RESET})") (class "Default")
      (node (ref "IC7") (pin "19") (pinfunction "~{RESET}_19") (pintype "input"))
      (node (ref "R14") (pin "2") (pinfunction "2_2") (pintype "passive"))
      (node (ref "R17") (pin "1") (pinfunction "1_1") (pintype "passive"))
    )
    (net (code "49") (name "Net-(J2-PadVBUS)") (class "Default")
      (node (ref "J2") (pin "VBUS") (pinfunction "VBUS_VBUS") (pintype "power_in"))
      (node (ref "R17") (pin "2") (pinfunction "2_2") (pintype "passive"))
    )
    (net (code "50") (name "Net-(LED1-PadA)") (class "Default")
      (node (ref "LED1") (pin "A") (pinfunction "A_A") (pintype "passive"))
      (node (ref "R18") (pin "1") (pinfunction "1_1") (pintype "passive"))
    )
    (net (code "51") (name "Net-(LED2-PadA)") (class "Default")
      (node (ref "LED2") (pin "A") (pinfunction "A_A") (pintype "passive"))
      (node (ref "R19") (pin "1") (pinfunction "1_1") (pintype "passive"))
    )
    (net (code "52") (name "Net-(LED6-PadA)") (class "Default")
      (node (ref "LED6") (pin "A") (pinfunction "A_A") (pintype "passive"))
      (node (ref "R13") (pin "1") (pinfunction "1_1") (pintype "passive"))
    )
    (net (code "53") (name "Net-(LED7-PadA)") (class "Default")
      (node (ref "LED7") (pin "A") (pinfunction "A_A") (pintype "passive"))
      (node (ref "R11") (pin "1") (pinfunction "1_1") (pintype "passive"))
    )
    (net (code "54") (name "Net-(LED8-PadA)") (class "Default")
      (node (ref "LED8") (pin "A") (pinfunction "A_A") (pintype "passive"))
      (node (ref "R27") (pin "1") (pinfunction "1_1") (pintype "passive"))
    )
    (net (code "55") (name "Net-(R31-Pad1)") (class "Default")
      (node (ref "R31") (pin "1") (pinfunction "1_1") (pintype "passive"))
      (node (ref "SV5") (pin "2") (pinfunction "2_2") (pintype "passive"))
    )
    (net (code "56") (name "RESET") (class "Default")
      (node (ref "C24") (pin "2") (pinfunction "2_2") (pintype "passive"))
      (node (ref "IC6") (pin "1") (pinfunction "PC6(/RESET)_1") (pintype "bidirectional"))
      (node (ref "R12") (pin "1") (pinfunction "1_1") (pintype "passive"))
      (node (ref "S1") (pin "1") (pinfunction "S_1") (pintype "passive"))
      (node (ref "S1") (pin "2") (pinfunction "S1_2") (pintype "passive"))
      (node (ref "SV1") (pin "5") (pinfunction "5_5") (pintype "passive"))
    )
    (net (code "57") (name "RX") (class "Default")
      (node (ref "IC6") (pin "2") (pinfunction "PD0(RXD)_2") (pintype "bidirectional"))
      (node (ref "IC7") (pin "1") (pinfunction "TXD_1") (pintype "output"))
    )
    (net (code "58") (name "R_CLOCK") (class "Default")
      (node (ref "IC3") (pin "18") (pinfunction "CLOCK_18") (pintype "input"))
      (node (ref "IC6") (pin "5") (pinfunction "PD3(INT1)_5") (pintype "bidirectional"))
    )
    (net (code "59") (name "R_CW{slash}CCW") (class "Default")
      (node (ref "IC3") (pin "17") (pinfunction "CW/CCW_17") (pintype "input"))
      (node (ref "IC6") (pin "6") (pinfunction "PD4(XCK/T0)_6") (pintype "bidirectional"))
    )
    (net (code "60") (name "R_ENABLE") (class "Default")
      (node (ref "IC3") (pin "10") (pinfunction "ENABLE_10") (pintype "input"))
      (node (ref "IC6") (pin "4") (pinfunction "PD2(INT0)_4") (pintype "bidirectional"))
    )
    (net (code "61") (name "SCK") (class "Default")
      (node (ref "IC6") (pin "19") (pinfunction "PB5(SCK)_19") (pintype "bidirectional"))
      (node (ref "R13") (pin "2") (pinfunction "2_2") (pintype "passive"))
      (node (ref "SV1") (pin "3") (pinfunction "3_3") (pintype "passive"))
    )
    (net (code "62") (name "SCL") (class "Default")
      (node (ref "IC6") (pin "28") (pinfunction "PC5(ADC5/SCL)_28") (pintype "bidirectional"))
      (node (ref "SV4") (pin "3") (pinfunction "3_3") (pintype "passive"))
    )
    (net (code "63") (name "SDA") (class "Default")
      (node (ref "IC6") (pin "27") (pinfunction "PC4(ADC4/SDA)_27") (pintype "bidirectional"))
      (node (ref "SV4") (pin "2") (pinfunction "2_2") (pintype "passive"))
    )
    (net (code "64") (name "SENS1_L") (class "Default")
      (node (ref "IC1") (pin "14") (pinfunction "SENS1_14") (pintype "output"))
      (node (ref "IC2") (pin "1") (pinfunction "SEN_A_1") (pintype "input"))
      (node (ref "R15") (pin "1") (pinfunction "1_1") (pintype "passive"))
      (node (ref "R20") (pin "1") (pinfunction "1_1") (pintype "passive"))
    )
    (net (code "65") (name "SENS1_R") (class "Default")
      (node (ref "IC3") (pin "14") (pinfunction "SENS1_14") (pintype "output"))
      (node (ref "IC4") (pin "1") (pinfunction "SEN_A_1") (pintype "input"))
      (node (ref "R22") (pin "1") (pinfunction "1_1") (pintype "passive"))
      (node (ref "R25") (pin "1") (pinfunction "1_1") (pintype "passive"))
    )
    (net (code "66") (name "SENS2_L") (class "Default")
      (node (ref "IC1") (pin "13") (pinfunction "SENS2_13") (pintype "output"))
      (node (ref "IC2") (pin "15") (pinfunction "SEN_B_15") (pintype "input"))
      (node (ref "R16") (pin "1") (pinfunction "1_1") (pintype "passive"))
      (node (ref "R21") (pin "1") (pinfunction "1_1") (pintype "passive"))
    )
    (net (code "67") (name "SENS2_R") (class "Default")
      (node (ref "IC3") (pin "13") (pinfunction "SENS2_13") (pintype "output"))
      (node (ref "IC4") (pin "15") (pinfunction "SEN_B_15") (pintype "input"))
      (node (ref "R23") (pin "1") (pinfunction "1_1") (pintype "passive"))
      (node (ref "R26") (pin "1") (pinfunction "1_1") (pintype "passive"))
    )
    (net (code "68") (name "TX") (class "Default")
      (node (ref "IC6") (pin "3") (pinfunction "PD1(TXD)_3") (pintype "bidirectional"))
      (node (ref "IC7") (pin "5") (pinfunction "RXD_5") (pintype "input"))
    )
    (net (code "69") (name "US1") (class "Default")
      (node (ref "IC6") (pin "26") (pinfunction "PC3(ADC3)_26") (pintype "bidirectional"))
      (node (ref "R30") (pin "1") (pinfunction "1_1") (pintype "passive"))
      (node (ref "R31") (pin "2") (pinfunction "2_2") (pintype "passive"))
    )
    (net (code "70") (name "unconnected-(IC1-HOME-Pad3)") (class "Default")
      (node (ref "IC1") (pin "3") (pinfunction "HOME_3") (pintype "output"))
    )
    (net (code "71") (name "unconnected-(IC1-SYNC-Pad1)") (class "Default")
      (node (ref "IC1") (pin "1") (pinfunction "SYNC_1") (pintype "output"))
    )
    (net (code "72") (name "unconnected-(IC3-HOME-Pad3)") (class "Default")
      (node (ref "IC3") (pin "3") (pinfunction "HOME_3") (pintype "output"))
    )
    (net (code "73") (name "unconnected-(IC3-SYNC-Pad1)") (class "Default")
      (node (ref "IC3") (pin "1") (pinfunction "SYNC_1") (pintype "output"))
    )
    (net (code "74") (name "unconnected-(IC7-CBUS0-Pad23)") (class "Default")
      (node (ref "IC7") (pin "23") (pinfunction "CBUS0_23") (pintype "bidirectional"))
    )
    (net (code "75") (name "unconnected-(IC7-CBUS1-Pad22)") (class "Default")
      (node (ref "IC7") (pin "22") (pinfunction "CBUS1_22") (pintype "bidirectional"))
    )
    (net (code "76") (name "unconnected-(IC7-CBUS2-Pad13)") (class "Default")
      (node (ref "IC7") (pin "13") (pinfunction "CBUS2_13") (pintype "bidirectional"))
    )
    (net (code "77") (name "unconnected-(IC7-CBUS3-Pad14)") (class "Default")
      (node (ref "IC7") (pin "14") (pinfunction "CBUS3_14") (pintype "bidirectional"))
    )
    (net (code "78") (name "unconnected-(IC7-CBUS4-Pad12)") (class "Default")
      (node (ref "IC7") (pin "12") (pinfunction "CBUS4_12") (pintype "bidirectional"))
    )
    (net (code "79") (name "unconnected-(IC7-OSCI-Pad27)") (class "Default")
      (node (ref "IC7") (pin "27") (pinfunction "OSCI_27") (pintype "input"))
    )
    (net (code "80") (name "unconnected-(IC7-OSCO-Pad28)") (class "Default")
      (node (ref "IC7") (pin "28") (pinfunction "OSCO_28") (pintype "output"))
    )
    (net (code "81") (name "unconnected-(IC7-~{CTS}-Pad11)") (class "Default")
      (node (ref "IC7") (pin "11") (pinfunction "~{CTS}_11") (pintype "input"))
    )
    (net (code "82") (name "unconnected-(IC7-~{DCD}-Pad10)") (class "Default")
      (node (ref "IC7") (pin "10") (pinfunction "~{DCD}_10") (pintype "input"))
    )
    (net (code "83") (name "unconnected-(IC7-~{DSR}-Pad9)") (class "Default")
      (node (ref "IC7") (pin "9") (pinfunction "~{DSR}_9") (pintype "input"))
    )
    (net (code "84") (name "unconnected-(IC7-~{RI}-Pad6)") (class "Default")
      (node (ref "IC7") (pin "6") (pinfunction "~{RI}_6") (pintype "input"))
    )
    (net (code "85") (name "unconnected-(IC7-~{RTS}-Pad3)") (class "Default")
      (node (ref "IC7") (pin "3") (pinfunction "~{RTS}_3") (pintype "output"))
    )
    (net (code "86") (name "unconnected-(J2-PadID)") (class "Default")
      (node (ref "J2") (pin "ID") (pinfunction "ID_ID") (pintype "bidirectional"))
    )
    (net (code "87") (name "unconnected-(SV2-Pad3)") (class "Default")
      (node (ref "SV2") (pin "3") (pinfunction "3_3") (pintype "passive"))
    )
    (net (code "88") (name "unconnected-(SV2-Pad4)") (class "Default")
      (node (ref "SV2") (pin "4") (pinfunction "4_4") (pintype "passive"))
    )
    (net (code "89") (name "unconnected-(SV3-Pad3)") (class "Default")
      (node (ref "SV3") (pin "3") (pinfunction "3_3") (pintype "passive"))
    )
    (net (code "90") (name "unconnected-(SV3-Pad4)") (class "Default")
      (node (ref "SV3") (pin "4") (pinfunction "4_4") (pintype "passive"))
    )
    (net (code "91") (name "unconnected-(X1-Pad2)") (class "Default")
      (node (ref "X1") (pin "2") (pinfunction "2_2") (pintype "passive"))
    )
    (net (code "92") (name "unconnected-(X1-Pad3)") (class "Default")
      (node (ref "X1") (pin "3") (pinfunction "3_3") (pintype "passive"))
    )
  )
)
